# jingle.net
KiCad netlist of a schematic drawn in EAGLE
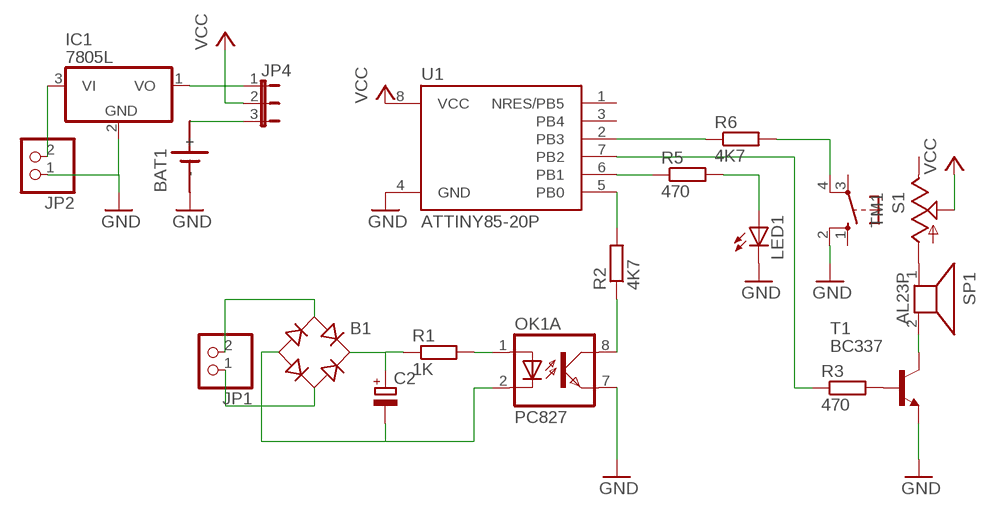
[diagram p0: schematic, sheet 1]

(export (version "E")
  (design (tool "Eeschema 10.0.6"))
  (components
    (comp (ref "B1")
      (value "RB1A")
      (footprint "eagle-import:RB1A")
      (libsource (lib "eagle-import") (part "RB1A"))
    )
    (comp (ref "BAT1")
      (value "SN2032")
      (footprint "eagle-import:SN2032")
      (libsource (lib "eagle-import") (part "SN2032"))
    )
    (comp (ref "C2")
      (value "CPOL-EUTT2D5L")
      (footprint "eagle-import:TT2D5L")
      (libsource (lib "eagle-import") (part "CPOL-EUTT2D5L"))
    )
    (comp (ref "IC1")
      (value "7805L")
      (footprint "eagle-import:TO92")
      (libsource (lib "eagle-import") (part "78L05"))
    )
    (comp (ref "JP1")
      (value "PINHD-1X2")
      (footprint "eagle-import:1X02")
      (libsource (lib "eagle-import") (part "PINHD-1X2"))
    )
    (comp (ref "JP2")
      (value "PINHD-1X2")
      (footprint "eagle-import:1X02")
      (libsource (lib "eagle-import") (part "PINHD-1X2"))
    )
    (comp (ref "JP4")
      (value "JP2E")
      (footprint "eagle-import:JP2")
      (libsource (lib "eagle-import") (part "JP2E"))
    )
    (comp (ref "LED1")
      (value "LED3MM")
      (footprint "eagle-import:LED3MM")
      (libsource (lib "eagle-import") (part "LED3MM"))
    )
    (comp (ref "OK1")
      (value "PC827")
      (footprint "eagle-import:DIL08")
      (libsource (lib "eagle-import") (part "PC827"))
    )
    (comp (ref "R1")
      (value "1K")
      (footprint "eagle-import:0207_7")
      (libsource (lib "eagle-import") (part "R-EU_0207/7"))
    )
    (comp (ref "R2")
      (value "4K7")
      (footprint "eagle-import:0207_7")
      (libsource (lib "eagle-import") (part "R-EU_0207/7"))
    )
    (comp (ref "R3")
      (value "470")
      (footprint "eagle-import:0207_7")
      (libsource (lib "eagle-import") (part "R-EU_0207/7"))
    )
    (comp (ref "R5")
      (value "470")
      (footprint "eagle-import:0207_7")
      (libsource (lib "eagle-import") (part "R-EU_0207/7"))
    )
    (comp (ref "R6")
      (value "4K7")
      (footprint "eagle-import:0207_7")
      (libsource (lib "eagle-import") (part "R-EU_0207/7"))
    )
    (comp (ref "S1")
      (value "10-XX")
      (footprint "eagle-import:B3F-10XX")
      (fields (field (name "MPN") "B3F-1000"))
      (libsource (lib "eagle-import") (part "10-XX"))
    )
    (comp (ref "SP1")
      (value "AL23P")
      (footprint "eagle-import:AL23P")
      (libsource (lib "eagle-import") (part "AL23P"))
    )
    (comp (ref "T1")
      (value "BC337")
      (footprint "eagle-import:TO92")
      (libsource (lib "eagle-import") (part "BC337"))
    )
    (comp (ref "TM1")
      (value "TRIM")
      (footprint "eagle-import:6MM")
      (libsource (lib "eagle-import") (part "TRIM"))
    )
    (comp (ref "U1")
      (value "ATTINY85-20P")
      (footprint "eagle-import:PDIP08_300MIL")
      (libsource (lib "eagle-import") (part "ATTINY85P-20"))
    )
  )
  (nets
    (net (code "1") (name "GND") (class "Default")
      (node (ref "BAT1") (pin "-") (pinfunction "-_-") (pintype "passive"))
      (node (ref "IC1") (pin "2") (pinfunction "GND_2") (pintype "passive"))
      (node (ref "JP2") (pin "1") (pinfunction "1_1") (pintype "passive"))
      (node (ref "LED1") (pin "K") (pinfunction "C_K") (pintype "passive"))
      (node (ref "OK1") (pin "7") (pinfunction "EMIT_7") (pintype "passive"))
      (node (ref "S1") (pin "2") (pinfunction "S1_2") (pintype "passive"))
      (node (ref "T1") (pin "1") (pinfunction "E_1") (pintype "passive"))
      (node (ref "U1") (pin "4") (pinfunction "GND_4") (pintype "power_in"))
    )
    (net (code "2") (name "Net-(B1-Pad+)") (class "Default")
      (node (ref "B1") (pin "+") (pinfunction "+_+") (pintype "passive"))
      (node (ref "C2") (pin "+") (pinfunction "+_+") (pintype "passive"))
      (node (ref "R1") (pin "1") (pinfunction "1_1") (pintype "passive"))
    )
    (net (code "3") (name "Net-(B1-PadAC1)") (class "Default")
      (node (ref "B1") (pin "AC1") (pinfunction "AC1_AC1") (pintype "passive"))
      (node (ref "JP1") (pin "2") (pinfunction "2_2") (pintype "passive"))
    )
    (net (code "4") (name "Net-(B1-PadAC2)") (class "Default")
      (node (ref "B1") (pin "AC2") (pinfunction "AC2_AC2") (pintype "passive"))
      (node (ref "JP1") (pin "1") (pinfunction "1_1") (pintype "passive"))
    )
    (net (code "5") (name "Net-(BAT1-Pad+)") (class "Default")
      (node (ref "BAT1") (pin "+") (pinfunction "+_+") (pintype "passive"))
      (node (ref "JP4") (pin "3") (pinfunction "3_3") (pintype "passive"))
    )
    (net (code "6") (name "Net-(IC1-VI)") (class "Default")
      (node (ref "IC1") (pin "3") (pinfunction "VI_3") (pintype "input"))
      (node (ref "JP2") (pin "2") (pinfunction "2_2") (pintype "passive"))
    )
    (net (code "7") (name "Net-(IC1-VO)") (class "Default")
      (node (ref "IC1") (pin "1") (pinfunction "VO_1") (pintype "passive"))
      (node (ref "JP4") (pin "1") (pinfunction "1_1") (pintype "passive"))
    )
    (net (code "8") (name "Net-(LED1-PadA)") (class "Default")
      (node (ref "LED1") (pin "A") (pinfunction "A_A") (pintype "passive"))
      (node (ref "R5") (pin "2") (pinfunction "2_2") (pintype "passive"))
    )
    (net (code "9") (name "Net-(OK1A-A)") (class "Default")
      (node (ref "OK1") (pin "1") (pinfunction "A_1") (pintype "passive"))
      (node (ref "R1") (pin "2") (pinfunction "2_2") (pintype "passive"))
    )
    (net (code "10") (name "Net-(OK1A-C)") (class "Default")
      (node (ref "B1") (pin "-") (pinfunction "-_-") (pintype "passive"))
      (node (ref "C2") (pin "-") (pinfunction "-_-") (pintype "passive"))
      (node (ref "OK1") (pin "2") (pinfunction "C_2") (pintype "passive"))
    )
    (net (code "11") (name "Net-(OK1A-COL)") (class "Default")
      (node (ref "OK1") (pin "8") (pinfunction "COL_8") (pintype "passive"))
      (node (ref "R2") (pin "1") (pinfunction "1_1") (pintype "passive"))
    )
    (net (code "12") (name "Net-(S1-P1)") (class "Default")
      (node (ref "R6") (pin "2") (pinfunction "2_2") (pintype "passive"))
      (node (ref "S1") (pin "4") (pinfunction "P1_4") (pintype "passive"))
    )
    (net (code "13") (name "Net-(SP1-Pad1)") (class "Default")
      (node (ref "SP1") (pin "1") (pinfunction "1_1") (pintype "passive"))
      (node (ref "TM1") (pin "A") (pinfunction "A_A") (pintype "passive"))
    )
    (net (code "14") (name "Net-(T1-B)") (class "Default")
      (node (ref "R3") (pin "2") (pinfunction "2_2") (pintype "passive"))
      (node (ref "T1") (pin "2") (pinfunction "B_2") (pintype "passive"))
    )
    (net (code "15") (name "Net-(T1-C)") (class "Default")
      (node (ref "SP1") (pin "2") (pinfunction "2_2") (pintype "passive"))
      (node (ref "T1") (pin "3") (pinfunction "C_3") (pintype "passive"))
    )
    (net (code "16") (name "Net-(U1-PB0)") (class "Default")
      (node (ref "R2") (pin "2") (pinfunction "2_2") (pintype "passive"))
      (node (ref "U1") (pin "5") (pinfunction "PB0_5") (pintype "bidirectional"))
    )
    (net (code "17") (name "Net-(U1-PB1)") (class "Default")
      (node (ref "R5") (pin "1") (pinfunction "1_1") (pintype "passive"))
      (node (ref "U1") (pin "6") (pinfunction "PB1_6") (pintype "bidirectional"))
    )
    (net (code "18") (name "Net-(U1-PB2)") (class "Default")
      (node (ref "R3") (pin "1") (pinfunction "1_1") (pintype "passive"))
      (node (ref "U1") (pin "7") (pinfunction "PB2_7") (pintype "bidirectional"))
    )
    (net (code "19") (name "Net-(U1-PB3)") (class "Default")
      (node (ref "R6") (pin "1") (pinfunction "1_1") (pintype "passive"))
      (node (ref "U1") (pin "2") (pinfunction "PB3_2") (pintype "bidirectional"))
    )
    (net (code "20") (name "VCC") (class "Default")
      (node (ref "JP4") (pin "2") (pinfunction "2_2") (pintype "passive"))
      (node (ref "TM1") (pin "S") (pinfunction "S_S") (pintype "passive"))
      (node (ref "U1") (pin "8") (pinfunction "VCC_8") (pintype "power_in"))
    )
    (net (code "21") (name "unconnected-(S1-P-Pad3)") (class "Default")
      (node (ref "S1") (pin "3") (pinfunction "P_3") (pintype "passive"))
    )
    (net (code "22") (name "unconnected-(S1-S-Pad1)") (class "Default")
      (node (ref "S1") (pin "1") (pinfunction "S_1") (pintype "passive"))
    )
    (net (code "23") (name "unconnected-(TM1-PadE)") (class "Default")
      (node (ref "TM1") (pin "E") (pinfunction "E_E") (pintype "passive"))
    )
    (net (code "24") (name "unconnected-(U1-NRES{slash}PB5-Pad1)") (class "Default")
      (node (ref "U1") (pin "1") (pinfunction "NRES/PB5_1") (pintype "bidirectional"))
    )
    (net (code "25") (name "unconnected-(U1-PB4-Pad3)") (class "Default")
      (node (ref "U1") (pin "3") (pinfunction "PB4_3") (pintype "bidirectional"))
    )
  )
)
